# suns_wifi_egse_power_supply.net
KiCad netlist of a schematic drawn in Altium Designer
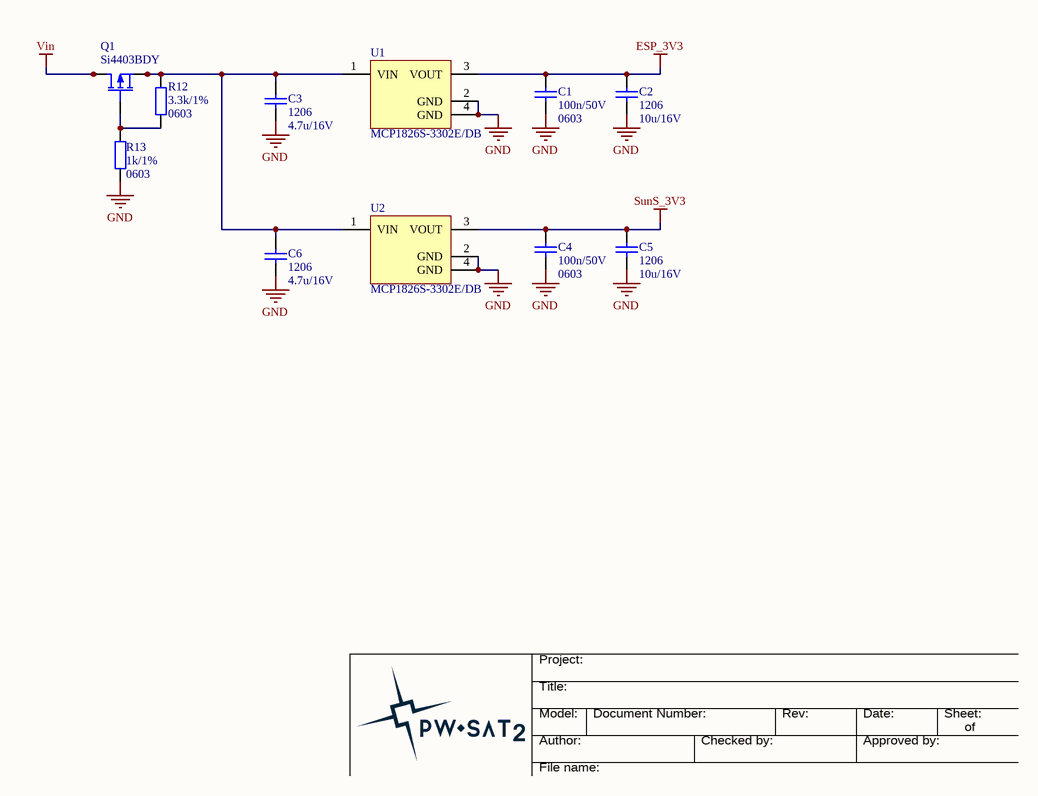
[diagram p0: suns_wifi_egse_power_supply.SchDoc]

(export (version "E")
  (design (tool "Eeschema 10.0.6"))
  (components
    (comp (ref "C1")
      (value "100n/50V")
      (footprint "SMD_Capacitor_0603")
      (description "Ceramic Cap Kemet COTS 100n/50V X7R 0603")
      (fields
        (field (name "MANUFACTURER") "Kemet")
        (field (name "MANUFACTURERPARTNUMBER") "C0603T104K5RALTU")
        (field (name "PACKAGE") "0603")
      )
      (libsource (lib "capacitors") (part "Cer_C0603T104K5RALTU"))
    )
    (comp (ref "C2")
      (value "10u/16V")
      (footprint "SMD_Capacitor_1206")
      (description "Ceramic Cap Kemet COTS 10u/16V X7R 1206")
      (fields
        (field (name "MANUFACTURERPARTNUMBER") "C1206T106K4RACTU")
        (field (name "MANUFACTURER") "Kemet")
        (field (name "PACKGE") "1206")
      )
      (libsource (lib "capacitors") (part "Cer_C1206T106K4RACTU"))
    )
    (comp (ref "C3")
      (value "4.7u/16V")
      (footprint "SMD_Capacitor_1206")
      (description "Ceramic Cap Kemet COTS 10u/16V X7R 1206")
      (fields
        (field (name "MANUFACTURERPARTNUMBER") "C1206T106K4RACTU")
        (field (name "MANUFACTURER") "Kemet")
        (field (name "PACKGE") "1206")
      )
      (libsource (lib "capacitors") (part "Cer_C1206T106K4RACTU"))
    )
    (comp (ref "C4")
      (value "100n/50V")
      (footprint "SMD_Capacitor_0603")
      (description "Ceramic Cap Kemet COTS 100n/50V X7R 0603")
      (fields
        (field (name "MANUFACTURER") "Kemet")
        (field (name "MANUFACTURERPARTNUMBER") "C0603T104K5RALTU")
        (field (name "PACKAGE") "0603")
      )
      (libsource (lib "capacitors") (part "Cer_C0603T104K5RALTU"))
    )
    (comp (ref "C5")
      (value "10u/16V")
      (footprint "SMD_Capacitor_1206")
      (description "Ceramic Cap Kemet COTS 10u/16V X7R 1206")
      (fields
        (field (name "MANUFACTURERPARTNUMBER") "C1206T106K4RACTU")
        (field (name "MANUFACTURER") "Kemet")
        (field (name "PACKGE") "1206")
      )
      (libsource (lib "capacitors") (part "Cer_C1206T106K4RACTU"))
    )
    (comp (ref "C6")
      (value "4.7u/16V")
      (footprint "SMD_Capacitor_1206")
      (description "Ceramic Cap Kemet COTS 10u/16V X7R 1206")
      (fields
        (field (name "MANUFACTURERPARTNUMBER") "C1206T106K4RACTU")
        (field (name "MANUFACTURER") "Kemet")
        (field (name "PACKGE") "1206")
      )
      (libsource (lib "capacitors") (part "Cer_C1206T106K4RACTU"))
    )
    (comp (ref "Q1")
      (value "Si4403BDY")
      (footprint "SOIC-8_M")
      (description "P-Channel 1.8 V (G-S) MOSFET")
      (libsource (lib "GG") (part "Si4403BDY"))
    )
    (comp (ref "R12")
      (value "3.3k/1%")
      (footprint "SMD_Resistor_0603")
      (description "1k/1% Vishay CRCW 0603 Resistor. 100mW, 100ppm, 75V.")
      (fields
        (field (name "MANUFACTURER") "Vishay")
        (field (name "MANUFACTURERPARTNUMBER") "CRCW06031K00FKxxxx")
        (field (name "PACKAGE") "0603")
      )
      (libsource (lib "resistors") (part "CRCW06031K00FKxxxx"))
    )
    (comp (ref "R13")
      (value "1k/1%")
      (footprint "SMD_Resistor_0603")
      (description "1k/1% Vishay CRCW 0603 Resistor. 100mW, 100ppm, 75V.")
      (fields
        (field (name "MANUFACTURER") "Vishay")
        (field (name "MANUFACTURERPARTNUMBER") "CRCW06031K00FKxxxx")
        (field (name "PACKAGE") "0603")
      )
      (libsource (lib "resistors") (part "CRCW06031K00FKxxxx"))
    )
    (comp (ref "U1")
      (value "MCP1826S-3302E/DB")
      (footprint "SOT-223-DB3_M")
      (description "1000 mA, Low Voltage, Low Quiescent Current LDO Regulator, 3-Pin SOT-223, Extended Temperature")
      (fields (field (name "MANUFACTURER") "Microchip"))
      (libsource (lib "microcircuits") (part "MCP1826S-3302E/DB"))
    )
    (comp (ref "U2")
      (value "MCP1826S-3302E/DB")
      (footprint "SOT-223-DB3_M")
      (description "1000 mA, Low Voltage, Low Quiescent Current LDO Regulator, 3-Pin SOT-223, Extended Temperature")
      (fields (field (name "MANUFACTURER") "Microchip"))
      (libsource (lib "microcircuits") (part "MCP1826S-3302E/DB"))
    )
  )
  (nets
    (net (code "1") (name "ESP_3V3") (class "Default")
      (node (ref "C1") (pin "1") (pinfunction "1_1") (pintype "passive"))
      (node (ref "C2") (pin "1") (pinfunction "1_1") (pintype "passive"))
      (node (ref "U1") (pin "3") (pinfunction "VOUT_3") (pintype "power_in"))
    )
    (net (code "2") (name "GND") (class "Default")
      (node (ref "C1") (pin "2") (pinfunction "2_2") (pintype "passive"))
      (node (ref "C2") (pin "2") (pinfunction "2_2") (pintype "passive"))
      (node (ref "C3") (pin "2") (pinfunction "2_2") (pintype "passive"))
      (node (ref "C4") (pin "2") (pinfunction "2_2") (pintype "passive"))
      (node (ref "C5") (pin "2") (pinfunction "2_2") (pintype "passive"))
      (node (ref "C6") (pin "2") (pinfunction "2_2") (pintype "passive"))
      (node (ref "R13") (pin "2") (pinfunction "2_2") (pintype "passive"))
      (node (ref "U1") (pin "2") (pinfunction "GND_2") (pintype "power_in"))
      (node (ref "U1") (pin "4") (pinfunction "GND_4") (pintype "power_in"))
      (node (ref "U2") (pin "2") (pinfunction "GND_2") (pintype "power_in"))
      (node (ref "U2") (pin "4") (pinfunction "GND_4") (pintype "power_in"))
    )
    (net (code "3") (name "Net-(Q1-G)") (class "Default")
      (node (ref "Q1") (pin "4") (pinfunction "G_4") (pintype "passive"))
      (node (ref "R12") (pin "2") (pinfunction "2_2") (pintype "passive"))
      (node (ref "R13") (pin "1") (pinfunction "1_1") (pintype "passive"))
    )
    (net (code "4") (name "Net-(U1-VIN)") (class "Default")
      (node (ref "C3") (pin "1") (pinfunction "1_1") (pintype "passive"))
      (node (ref "C6") (pin "1") (pinfunction "1_1") (pintype "passive"))
      (node (ref "Q1") (pin "1") (pinfunction "S_1") (pintype "passive"))
      (node (ref "Q1") (pin "2") (pinfunction "S_2") (pintype "passive"))
      (node (ref "Q1") (pin "3") (pinfunction "S_3") (pintype "passive"))
      (node (ref "R12") (pin "1") (pinfunction "1_1") (pintype "passive"))
      (node (ref "U1") (pin "1") (pinfunction "VIN_1") (pintype "power_in"))
      (node (ref "U2") (pin "1") (pinfunction "VIN_1") (pintype "power_in"))
    )
    (net (code "5") (name "SunS_3V3") (class "Default")
      (node (ref "C4") (pin "1") (pinfunction "1_1") (pintype "passive"))
      (node (ref "C5") (pin "1") (pinfunction "1_1") (pintype "passive"))
      (node (ref "U2") (pin "3") (pinfunction "VOUT_3") (pintype "power_in"))
    )
    (net (code "6") (name "Vin") (class "Default")
      (node (ref "Q1") (pin "5") (pinfunction "D_5") (pintype "passive"))
      (node (ref "Q1") (pin "6") (pinfunction "D_6") (pintype "passive"))
      (node (ref "Q1") (pin "7") (pinfunction "D_7") (pintype "passive"))
      (node (ref "Q1") (pin "8") (pinfunction "D_8") (pintype "passive"))
    )
  )
)
